# Sensors.net
KiCad netlist of a schematic drawn in Altium Designer
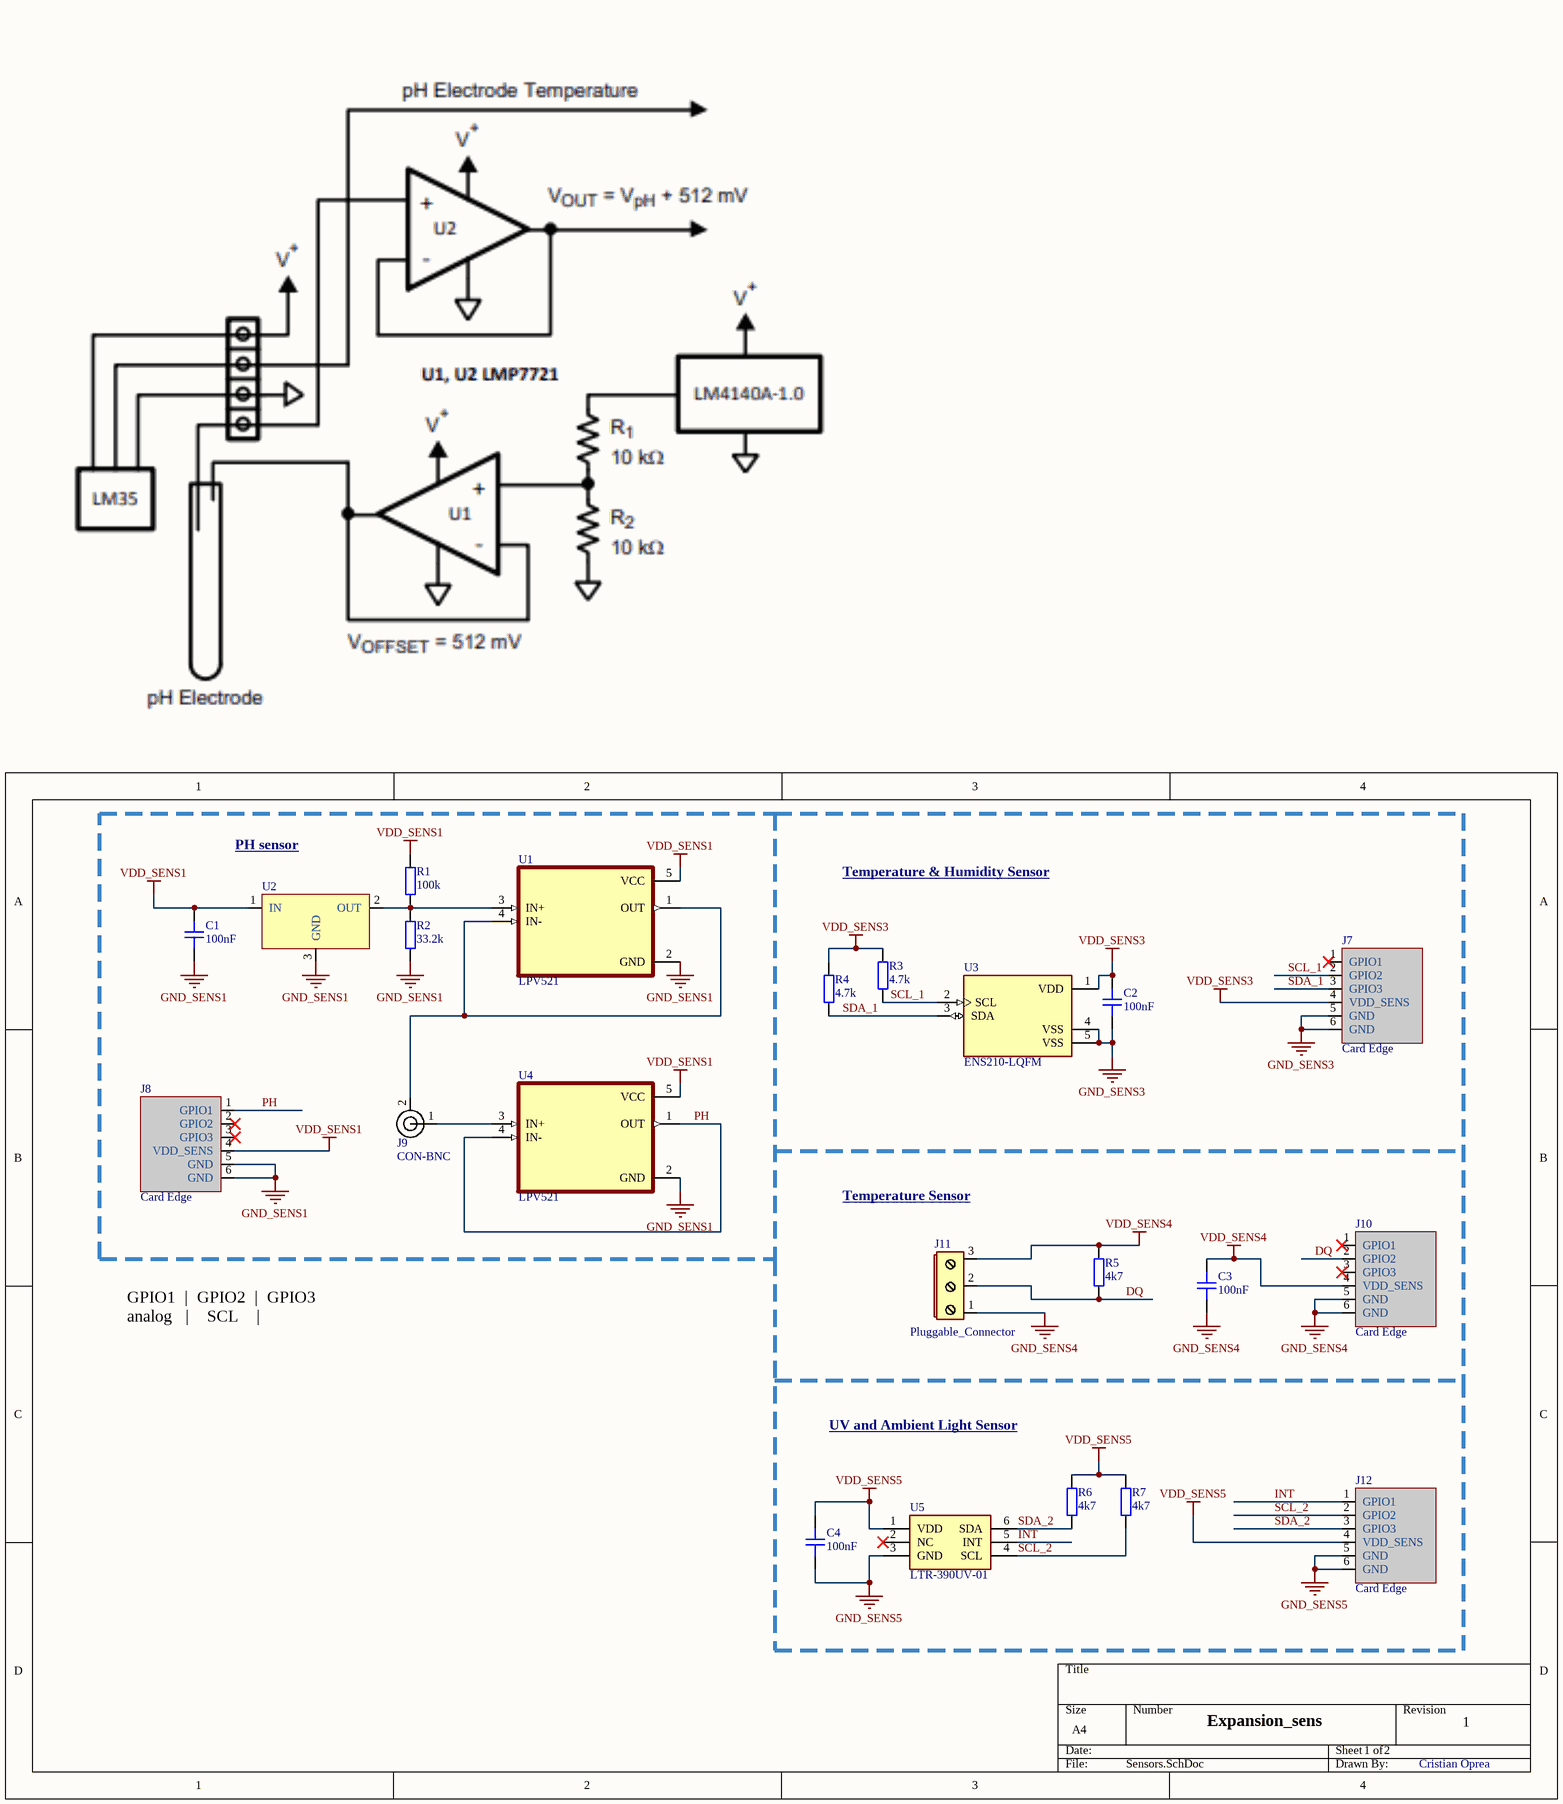
[diagram p0: Sensors.SchDoc]

(export (version "E")
  (design (tool "Eeschema 10.0.6"))
  (components
    (comp (ref "C1")
      (value "100nF")
      (footprint "C0603")
      (description "Capacitor SMD 0603")
      (libsource (lib "Schlib1") (part "CAP_0603"))
    )
    (comp (ref "C2")
      (value "100nF")
      (footprint "C0603")
      (description "Capacitor SMD 0603")
      (libsource (lib "Schlib1") (part "CAP_0603"))
    )
    (comp (ref "C3")
      (value "100nF")
      (footprint "C0603")
      (description "Capacitor SMD 0603")
      (libsource (lib "Schlib1") (part "CAP_0603"))
    )
    (comp (ref "C4")
      (value "100nF")
      (footprint "C0603")
      (description "Capacitor SMD 0603")
      (libsource (lib "Schlib1") (part "CAP_0603"))
    )
    (comp (ref "J7")
      (value "Card Edge")
      (footprint "Card Edge")
      (description "Card Edge pads for 2.54 mm pitch edge connector")
      (libsource (lib "Schlib1") (part "Card Edge"))
    )
    (comp (ref "J8")
      (value "Card Edge")
      (footprint "Card Edge")
      (description "Card Edge pads for 2.54 mm pitch edge connector")
      (libsource (lib "") (part "Card Edge_1"))
    )
    (comp (ref "J9")
      (value "CON-BNC")
      (footprint "CON_BNC_MOLEX_0731375003")
      (description "RF Connector BNC Female 50 Ohms PCB TH Mount")
      (fields
        (field (name "MANUFACTURER") "RF Solutions")
        (field (name "MANUFACTURER PART NUMBER") "CON-SMA-EDGE-S")
      )
      (libsource (lib "Schlib1") (part "CON-BNC"))
    )
    (comp (ref "J10")
      (value "Card Edge")
      (footprint "Card Edge")
      (description "Card Edge pads for 2.54 mm pitch edge connector")
      (libsource (lib "Schlib1") (part "Card Edge"))
    )
    (comp (ref "J11")
      (value "Pluggable_Connector")
      (footprint "5mm_screw_terminal_3_pos")
      (description "Screw terminal or plug terminal")
      (libsource (lib "Schlib1") (part "Pluggable_Connector"))
    )
    (comp (ref "J12")
      (value "Card Edge")
      (footprint "Card Edge")
      (description "Card Edge pads for 2.54 mm pitch edge connector")
      (libsource (lib "Schlib1") (part "Card Edge"))
    )
    (comp (ref "R1")
      (value "100k")
      (footprint "R0603")
      (description "Resistor SMD 0603")
      (libsource (lib "Schlib1") (part "RES_0603"))
    )
    (comp (ref "R2")
      (value "33.2k")
      (footprint "R0603")
      (description "Resistor SMD 0603")
      (libsource (lib "Schlib1") (part "RES_0603"))
    )
    (comp (ref "R3")
      (value "4.7k")
      (footprint "R0603")
      (description "Resistor SMD 0603")
      (libsource (lib "Schlib1") (part "RES_0603"))
    )
    (comp (ref "R4")
      (value "4.7k")
      (footprint "R0603")
      (description "Resistor SMD 0603")
      (libsource (lib "Schlib1") (part "RES_0603"))
    )
    (comp (ref "R5")
      (value "4k7")
      (footprint "R0603")
      (description "Resistor SMD 0805")
      (libsource (lib "Schlib1") (part "RES_0805"))
    )
    (comp (ref "R6")
      (value "4k7")
      (footprint "R0603")
      (description "Resistor SMD 0805")
      (libsource (lib "Schlib1") (part "RES_0805"))
    )
    (comp (ref "R7")
      (value "4k7")
      (footprint "R0603")
      (description "Resistor SMD 0805")
      (libsource (lib "Schlib1") (part "RES_0805"))
    )
    (comp (ref "U1")
      (value "LPV521")
      (footprint "SOT65P210X110-5N")
      (fields (field (name "MP") "MAX4466EXK"))
      (libsource (lib "Schlib1") (part "LPV521"))
    )
    (comp (ref "U2")
      (value "ADR5040BKSZ-REEL7")
      (footprint "SOT23-3")
      (description "Voltage References 2.048 Low-Cost, Micropower, Low-Dropout, High-Output-Current, SOT23")
      (fields
        (field (name "MANUFACTURER") "Maxim Integrated")
        (field (name "MANUFACTURER PART NUMBER") "MAX6101EUR+T")
      )
      (libsource (lib "Schlib1") (part "VREF"))
    )
    (comp (ref "U3")
      (value "ENS210-LQFM")
      (footprint "XDCR_ENS210-LQFM")
      (description "Humidity/Temperature Sensor Digital Serial (2-Wire, I2C) 4-Pin QFN EP T/R")
      (fields (field (name "MF") "ScioSense"))
      (libsource (lib "Schlib1") (part "ENS210-LQFM"))
    )
    (comp (ref "U4")
      (value "LPV521")
      (footprint "SOT65P210X110-5N")
      (fields (field (name "MP") "MAX4466EXK"))
      (libsource (lib "Schlib1") (part "LPV521"))
    )
    (comp (ref "U5")
      (value "LTR-390UV-01")
      (footprint "LTR390-UV")
      (description "SENSOR OPT ULTRAVIOLET 6PINS")
      (fields (field (name "MOUSER PART NUMBER") "859-LTR390UV01"))
      (libsource (lib "Schlib1") (part "LTR-390UV-01"))
    )
  )
  (nets
    (net (code "1") (name "/DQ") (class "Default")
      (node (ref "J10") (pin "2") (pinfunction "GPIO2_2") (pintype "passive"))
      (node (ref "J11") (pin "2") (pinfunction "2_2") (pintype "passive"))
      (node (ref "R5") (pin "1") (pinfunction "1_1") (pintype "passive"))
    )
    (net (code "2") (name "/INT") (class "Default")
      (node (ref "J12") (pin "1") (pinfunction "GPIO1_1") (pintype "passive"))
      (node (ref "U5") (pin "5") (pinfunction "INT_5") (pintype "passive"))
    )
    (net (code "3") (name "/PH") (class "Default")
      (node (ref "J8") (pin "1") (pinfunction "GPIO1_1") (pintype "passive"))
      (node (ref "U4") (pin "1") (pinfunction "OUT_1") (pintype "output"))
      (node (ref "U4") (pin "4") (pinfunction "IN-_4") (pintype "input"))
    )
    (net (code "4") (name "/SCL_1") (class "Default")
      (node (ref "J7") (pin "2") (pinfunction "GPIO2_2") (pintype "passive"))
      (node (ref "R3") (pin "1") (pinfunction "1_1") (pintype "passive"))
      (node (ref "U3") (pin "2") (pinfunction "SCL_2") (pintype "input"))
    )
    (net (code "5") (name "/SCL_2") (class "Default")
      (node (ref "J12") (pin "2") (pinfunction "GPIO2_2") (pintype "passive"))
      (node (ref "R7") (pin "1") (pinfunction "1_1") (pintype "passive"))
      (node (ref "U5") (pin "4") (pinfunction "SCL_4") (pintype "passive"))
    )
    (net (code "6") (name "/SDA_1") (class "Default")
      (node (ref "J7") (pin "3") (pinfunction "GPIO3_3") (pintype "passive"))
      (node (ref "R4") (pin "2") (pinfunction "2_2") (pintype "passive"))
      (node (ref "U3") (pin "3") (pinfunction "SDA_3") (pintype "bidirectional"))
    )
    (net (code "7") (name "/SDA_2") (class "Default")
      (node (ref "J12") (pin "3") (pinfunction "GPIO3_3") (pintype "passive"))
      (node (ref "R6") (pin "1") (pinfunction "1_1") (pintype "passive"))
      (node (ref "U5") (pin "6") (pinfunction "SDA_6") (pintype "passive"))
    )
    (net (code "8") (name "GND_SENS1") (class "Default")
      (node (ref "C1") (pin "1") (pinfunction "1_1") (pintype "passive"))
      (node (ref "J8") (pin "5") (pinfunction "GND_5") (pintype "passive"))
      (node (ref "J8") (pin "6") (pinfunction "GND_6") (pintype "passive"))
      (node (ref "R2") (pin "1") (pinfunction "1_1") (pintype "passive"))
      (node (ref "U1") (pin "2") (pinfunction "GND_2") (pintype "power_in"))
      (node (ref "U2") (pin "3") (pinfunction "GND_3") (pintype "passive"))
      (node (ref "U4") (pin "2") (pinfunction "GND_2") (pintype "power_in"))
    )
    (net (code "9") (name "GND_SENS3") (class "Default")
      (node (ref "C2") (pin "1") (pinfunction "1_1") (pintype "passive"))
      (node (ref "J7") (pin "5") (pinfunction "GND_5") (pintype "passive"))
      (node (ref "J7") (pin "6") (pinfunction "GND_6") (pintype "passive"))
      (node (ref "U3") (pin "4") (pinfunction "VSS_4") (pintype "power_in"))
      (node (ref "U3") (pin "5") (pinfunction "VSS_5") (pintype "power_in"))
    )
    (net (code "10") (name "GND_SENS4") (class "Default")
      (node (ref "C3") (pin "1") (pinfunction "1_1") (pintype "passive"))
      (node (ref "J10") (pin "5") (pinfunction "GND_5") (pintype "passive"))
      (node (ref "J10") (pin "6") (pinfunction "GND_6") (pintype "passive"))
      (node (ref "J11") (pin "1") (pinfunction "1_1") (pintype "passive"))
    )
    (net (code "11") (name "GND_SENS5") (class "Default")
      (node (ref "C4") (pin "1") (pinfunction "1_1") (pintype "passive"))
      (node (ref "J12") (pin "5") (pinfunction "GND_5") (pintype "passive"))
      (node (ref "J12") (pin "6") (pinfunction "GND_6") (pintype "passive"))
      (node (ref "U5") (pin "3") (pinfunction "GND_3") (pintype "passive"))
    )
    (net (code "12") (name "Net-(U1-IN+)") (class "Default")
      (node (ref "R1") (pin "1") (pinfunction "1_1") (pintype "passive"))
      (node (ref "R2") (pin "2") (pinfunction "2_2") (pintype "passive"))
      (node (ref "U1") (pin "3") (pinfunction "IN+_3") (pintype "input"))
      (node (ref "U2") (pin "2") (pinfunction "OUT_2") (pintype "passive"))
    )
    (net (code "13") (name "Net-(U1-IN-)") (class "Default")
      (node (ref "J9") (pin "2") (pinfunction "2_2") (pintype "passive"))
      (node (ref "U1") (pin "1") (pinfunction "OUT_1") (pintype "output"))
      (node (ref "U1") (pin "4") (pinfunction "IN-_4") (pintype "input"))
    )
    (net (code "14") (name "Net-(U4-IN+)") (class "Default")
      (node (ref "J9") (pin "1") (pinfunction "1_1") (pintype "passive"))
      (node (ref "U4") (pin "3") (pinfunction "IN+_3") (pintype "input"))
    )
    (net (code "15") (name "VDD_SENS1") (class "Default")
      (node (ref "C1") (pin "2") (pinfunction "2_2") (pintype "passive"))
      (node (ref "J8") (pin "4") (pinfunction "VDD_SENS_4") (pintype "passive"))
      (node (ref "R1") (pin "2") (pinfunction "2_2") (pintype "passive"))
      (node (ref "U1") (pin "5") (pinfunction "VCC_5") (pintype "power_in"))
      (node (ref "U2") (pin "1") (pinfunction "IN_1") (pintype "passive"))
      (node (ref "U4") (pin "5") (pinfunction "VCC_5") (pintype "power_in"))
    )
    (net (code "16") (name "VDD_SENS3") (class "Default")
      (node (ref "C2") (pin "2") (pinfunction "2_2") (pintype "passive"))
      (node (ref "J7") (pin "4") (pinfunction "VDD_SENS_4") (pintype "passive"))
      (node (ref "R3") (pin "2") (pinfunction "2_2") (pintype "passive"))
      (node (ref "R4") (pin "1") (pinfunction "1_1") (pintype "passive"))
      (node (ref "U3") (pin "1") (pinfunction "VDD_1") (pintype "power_in"))
    )
    (net (code "17") (name "VDD_SENS4") (class "Default")
      (node (ref "C3") (pin "2") (pinfunction "2_2") (pintype "passive"))
      (node (ref "J10") (pin "4") (pinfunction "VDD_SENS_4") (pintype "passive"))
      (node (ref "J11") (pin "3") (pinfunction "3_3") (pintype "passive"))
      (node (ref "R5") (pin "2") (pinfunction "2_2") (pintype "passive"))
    )
    (net (code "18") (name "VDD_SENS5") (class "Default")
      (node (ref "C4") (pin "2") (pinfunction "2_2") (pintype "passive"))
      (node (ref "J12") (pin "4") (pinfunction "VDD_SENS_4") (pintype "passive"))
      (node (ref "R6") (pin "2") (pinfunction "2_2") (pintype "passive"))
      (node (ref "R7") (pin "2") (pinfunction "2_2") (pintype "passive"))
      (node (ref "U5") (pin "1") (pinfunction "VDD_1") (pintype "passive"))
    )
    (net (code "19") (name "unconnected-(J7-GPIO1-Pad1)") (class "Default")
      (node (ref "J7") (pin "1") (pinfunction "GPIO1_1") (pintype "passive+no_connect"))
    )
    (net (code "20") (name "unconnected-(J8-GPIO2-Pad2)") (class "Default")
      (node (ref "J8") (pin "2") (pinfunction "GPIO2_2") (pintype "passive+no_connect"))
    )
    (net (code "21") (name "unconnected-(J8-GPIO3-Pad3)") (class "Default")
      (node (ref "J8") (pin "3") (pinfunction "GPIO3_3") (pintype "passive+no_connect"))
    )
    (net (code "22") (name "unconnected-(J10-GPIO1-Pad1)") (class "Default")
      (node (ref "J10") (pin "1") (pinfunction "GPIO1_1") (pintype "passive+no_connect"))
    )
    (net (code "23") (name "unconnected-(J10-GPIO3-Pad3)") (class "Default")
      (node (ref "J10") (pin "3") (pinfunction "GPIO3_3") (pintype "passive+no_connect"))
    )
    (net (code "24") (name "unconnected-(U5-NC-Pad2)") (class "Default")
      (node (ref "U5") (pin "2") (pinfunction "NC_2") (pintype "passive+no_connect"))
    )
  )
)
